# design.net
KiCad netlist of a schematic drawn in Altium Designer
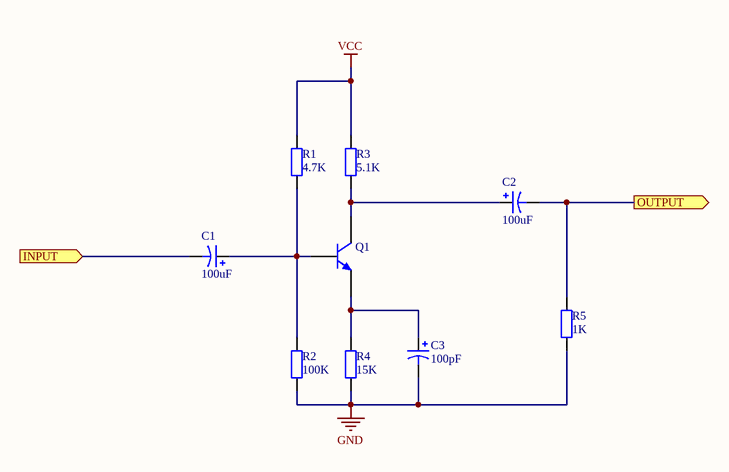
[diagram p0: 三极管放大电路.SchDoc]

(export (version "E")
  (design (tool "Eeschema 10.0.6"))
  (components
    (comp (ref "C1")
      (value "100uF")
      (footprint "RB7.6-15")
      (description "Polarized Capacitor (Radial)")
      (fields (field (name "Comment") "Cap Pol1") (field (name "PUBLISHER") "Altium Limited"))
      (libsource (lib "Miscellaneous Devices") (part "Cap Pol1"))
    )
    (comp (ref "C2")
      (value "100uF")
      (footprint "RB7.6-15")
      (description "Polarized Capacitor (Radial)")
      (fields (field (name "Comment") "Cap Pol1") (field (name "PUBLISHER") "Altium Limited"))
      (libsource (lib "Miscellaneous Devices") (part "Cap Pol1"))
    )
    (comp (ref "C3")
      (value "100pF")
      (footprint "RB7.6-15")
      (description "Polarized Capacitor (Radial)")
      (fields (field (name "Comment") "Cap Pol1") (field (name "PUBLISHER") "Altium Limited"))
      (libsource (lib "Miscellaneous Devices") (part "Cap Pol1"))
    )
    (comp (ref "Q1")
      (value "NPN")
      (footprint "TO-226-AA")
      (description "NPN Bipolar Transistor")
      (fields (field (name "PUBLISHER") "Altium Limited"))
      (libsource (lib "Miscellaneous Devices") (part "NPN"))
    )
    (comp (ref "R1")
      (value "4.7K")
      (footprint "AXIAL-0.4")
      (description "Resistor")
      (fields (field (name "Comment") "Res2") (field (name "PUBLISHER") "Altium Limited"))
      (libsource (lib "Miscellaneous Devices") (part "Res2"))
    )
    (comp (ref "R2")
      (value "100K")
      (footprint "AXIAL-0.4")
      (description "Resistor")
      (fields (field (name "Comment") "Res2") (field (name "PUBLISHER") "Altium Limited"))
      (libsource (lib "Miscellaneous Devices") (part "Res2"))
    )
    (comp (ref "R3")
      (value "5.1K")
      (footprint "AXIAL-0.4")
      (description "Resistor")
      (fields (field (name "Comment") "Res2") (field (name "PUBLISHER") "Altium Limited"))
      (libsource (lib "Miscellaneous Devices") (part "Res2"))
    )
    (comp (ref "R4")
      (value "15K")
      (footprint "AXIAL-0.4")
      (description "Resistor")
      (fields (field (name "Comment") "Res2") (field (name "PUBLISHER") "Altium Limited"))
      (libsource (lib "Miscellaneous Devices") (part "Res2"))
    )
    (comp (ref "R5")
      (value "1K")
      (footprint "AXIAL-0.4")
      (description "Resistor")
      (fields (field (name "Comment") "Res2") (field (name "PUBLISHER") "Altium Limited"))
      (libsource (lib "Miscellaneous Devices") (part "Res2"))
    )
  )
  (nets
    (net (code "1") (name "/INPUT") (class "Default")
      (node (ref "C1") (pin "2") (pinfunction "2_2") (pintype "passive"))
    )
    (net (code "2") (name "/OUTPUT") (class "Default")
      (node (ref "C2") (pin "2") (pinfunction "2_2") (pintype "passive"))
      (node (ref "R5") (pin "2") (pinfunction "2_2") (pintype "passive"))
    )
    (net (code "3") (name "GND") (class "Default")
      (node (ref "C3") (pin "2") (pinfunction "2_2") (pintype "passive"))
      (node (ref "R2") (pin "1") (pinfunction "1_1") (pintype "passive"))
      (node (ref "R4") (pin "1") (pinfunction "1_1") (pintype "passive"))
      (node (ref "R5") (pin "1") (pinfunction "1_1") (pintype "passive"))
    )
    (net (code "4") (name "Net-(Q1-B)") (class "Default")
      (node (ref "C1") (pin "1") (pinfunction "1_1") (pintype "passive"))
      (node (ref "Q1") (pin "2") (pinfunction "B_2") (pintype "passive"))
      (node (ref "R1") (pin "1") (pinfunction "1_1") (pintype "passive"))
      (node (ref "R2") (pin "2") (pinfunction "2_2") (pintype "passive"))
    )
    (net (code "5") (name "Net-(Q1-C)") (class "Default")
      (node (ref "C2") (pin "1") (pinfunction "1_1") (pintype "passive"))
      (node (ref "Q1") (pin "1") (pinfunction "C_1") (pintype "passive"))
      (node (ref "R3") (pin "1") (pinfunction "1_1") (pintype "passive"))
    )
    (net (code "6") (name "Net-(Q1-E)") (class "Default")
      (node (ref "C3") (pin "1") (pinfunction "1_1") (pintype "passive"))
      (node (ref "Q1") (pin "3") (pinfunction "E_3") (pintype "passive"))
      (node (ref "R4") (pin "2") (pinfunction "2_2") (pintype "passive"))
    )
    (net (code "7") (name "VCC") (class "Default")
      (node (ref "R1") (pin "2") (pinfunction "2_2") (pintype "passive"))
      (node (ref "R3") (pin "2") (pinfunction "2_2") (pintype "passive"))
    )
  )
)
